# TLC5955.net
KiCad netlist of a schematic drawn in Altium Designer
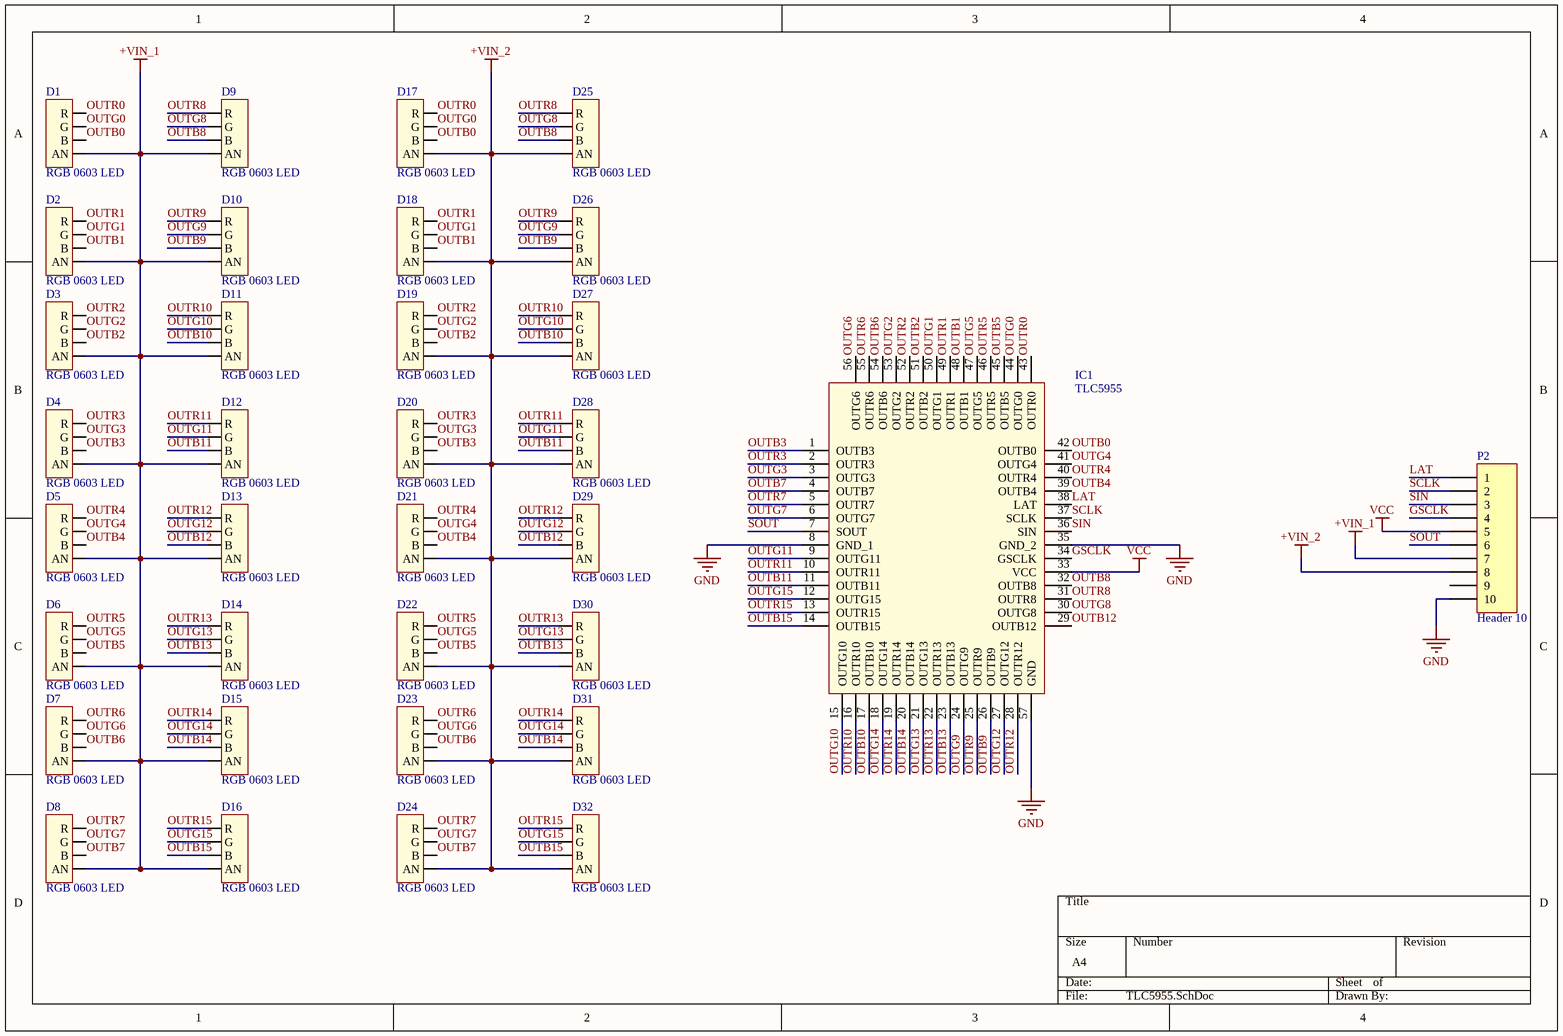
[diagram p0: TLC5955.SchDoc]

(export (version "E")
  (design (tool "Eeschema 10.0.6"))
  (components
    (comp (ref "D1")
      (value "RGB 0603 LED")
      (footprint "RGB LED")
      (libsource (lib "Schlib1") (part "RGB 0603 LED"))
    )
    (comp (ref "D2")
      (value "RGB 0603 LED")
      (footprint "RGB LED")
      (libsource (lib "Schlib1") (part "RGB 0603 LED"))
    )
    (comp (ref "D3")
      (value "RGB 0603 LED")
      (footprint "RGB LED")
      (libsource (lib "Schlib1") (part "RGB 0603 LED"))
    )
    (comp (ref "D4")
      (value "RGB 0603 LED")
      (footprint "RGB LED")
      (libsource (lib "Schlib1") (part "RGB 0603 LED"))
    )
    (comp (ref "D5")
      (value "RGB 0603 LED")
      (footprint "RGB LED")
      (libsource (lib "Schlib1") (part "RGB 0603 LED"))
    )
    (comp (ref "D6")
      (value "RGB 0603 LED")
      (footprint "RGB LED")
      (libsource (lib "Schlib1") (part "RGB 0603 LED"))
    )
    (comp (ref "D7")
      (value "RGB 0603 LED")
      (footprint "RGB LED")
      (libsource (lib "Schlib1") (part "RGB 0603 LED"))
    )
    (comp (ref "D8")
      (value "RGB 0603 LED")
      (footprint "RGB LED")
      (libsource (lib "Schlib1") (part "RGB 0603 LED"))
    )
    (comp (ref "D9")
      (value "RGB 0603 LED")
      (footprint "RGB LED")
      (libsource (lib "") (part "RGB 0603 LED_1"))
    )
    (comp (ref "D10")
      (value "RGB 0603 LED")
      (footprint "RGB LED")
      (libsource (lib "") (part "RGB 0603 LED_1"))
    )
    (comp (ref "D11")
      (value "RGB 0603 LED")
      (footprint "RGB LED")
      (libsource (lib "") (part "RGB 0603 LED_1"))
    )
    (comp (ref "D12")
      (value "RGB 0603 LED")
      (footprint "RGB LED")
      (libsource (lib "") (part "RGB 0603 LED_1"))
    )
    (comp (ref "D13")
      (value "RGB 0603 LED")
      (footprint "RGB LED")
      (libsource (lib "") (part "RGB 0603 LED_1"))
    )
    (comp (ref "D14")
      (value "RGB 0603 LED")
      (footprint "RGB LED")
      (libsource (lib "") (part "RGB 0603 LED_1"))
    )
    (comp (ref "D15")
      (value "RGB 0603 LED")
      (footprint "RGB LED")
      (libsource (lib "") (part "RGB 0603 LED_1"))
    )
    (comp (ref "D16")
      (value "RGB 0603 LED")
      (footprint "RGB LED")
      (libsource (lib "") (part "RGB 0603 LED_1"))
    )
    (comp (ref "D17")
      (value "RGB 0603 LED")
      (footprint "RGB LED")
      (libsource (lib "Schlib1") (part "RGB 0603 LED"))
    )
    (comp (ref "D18")
      (value "RGB 0603 LED")
      (footprint "RGB LED")
      (libsource (lib "Schlib1") (part "RGB 0603 LED"))
    )
    (comp (ref "D19")
      (value "RGB 0603 LED")
      (footprint "RGB LED")
      (libsource (lib "Schlib1") (part "RGB 0603 LED"))
    )
    (comp (ref "D20")
      (value "RGB 0603 LED")
      (footprint "RGB LED")
      (libsource (lib "Schlib1") (part "RGB 0603 LED"))
    )
    (comp (ref "D21")
      (value "RGB 0603 LED")
      (footprint "RGB LED")
      (libsource (lib "Schlib1") (part "RGB 0603 LED"))
    )
    (comp (ref "D22")
      (value "RGB 0603 LED")
      (footprint "RGB LED")
      (libsource (lib "Schlib1") (part "RGB 0603 LED"))
    )
    (comp (ref "D23")
      (value "RGB 0603 LED")
      (footprint "RGB LED")
      (libsource (lib "Schlib1") (part "RGB 0603 LED"))
    )
    (comp (ref "D24")
      (value "RGB 0603 LED")
      (footprint "RGB LED")
      (libsource (lib "Schlib1") (part "RGB 0603 LED"))
    )
    (comp (ref "D25")
      (value "RGB 0603 LED")
      (footprint "RGB LED")
      (libsource (lib "") (part "RGB 0603 LED_1"))
    )
    (comp (ref "D26")
      (value "RGB 0603 LED")
      (footprint "RGB LED")
      (libsource (lib "") (part "RGB 0603 LED_1"))
    )
    (comp (ref "D27")
      (value "RGB 0603 LED")
      (footprint "RGB LED")
      (libsource (lib "") (part "RGB 0603 LED_1"))
    )
    (comp (ref "D28")
      (value "RGB 0603 LED")
      (footprint "RGB LED")
      (libsource (lib "") (part "RGB 0603 LED_1"))
    )
    (comp (ref "D29")
      (value "RGB 0603 LED")
      (footprint "RGB LED")
      (libsource (lib "") (part "RGB 0603 LED_1"))
    )
    (comp (ref "D30")
      (value "RGB 0603 LED")
      (footprint "RGB LED")
      (libsource (lib "") (part "RGB 0603 LED_1"))
    )
    (comp (ref "D31")
      (value "RGB 0603 LED")
      (footprint "RGB LED")
      (libsource (lib "") (part "RGB 0603 LED_1"))
    )
    (comp (ref "D32")
      (value "RGB 0603 LED")
      (footprint "RGB LED")
      (libsource (lib "") (part "RGB 0603 LED_1"))
    )
    (comp (ref "IC1") (value "TLC5955") (footprint "TLC5955") (libsource (lib "Schlib1") (part "TLC5955")))
    (comp (ref "P2")
      (value "Header 10")
      (footprint "HDR1X10")
      (description "Header, 10-Pin")
      (fields (field (name "PUBLISHER") "Altium Limited"))
      (libsource (lib "Miscellaneous Connectors") (part "Header 10"))
    )
  )
  (nets
    (net (code "1") (name "+VIN_1") (class "Default")
      (node (ref "D1") (pin "4") (pinfunction "AN_4") (pintype "passive"))
      (node (ref "D10") (pin "4") (pinfunction "AN_4") (pintype "passive"))
      (node (ref "D11") (pin "4") (pinfunction "AN_4") (pintype "passive"))
      (node (ref "D12") (pin "4") (pinfunction "AN_4") (pintype "passive"))
      (node (ref "D13") (pin "4") (pinfunction "AN_4") (pintype "passive"))
      (node (ref "D14") (pin "4") (pinfunction "AN_4") (pintype "passive"))
      (node (ref "D15") (pin "4") (pinfunction "AN_4") (pintype "passive"))
      (node (ref "D16") (pin "4") (pinfunction "AN_4") (pintype "passive"))
      (node (ref "D2") (pin "4") (pinfunction "AN_4") (pintype "passive"))
      (node (ref "D3") (pin "4") (pinfunction "AN_4") (pintype "passive"))
      (node (ref "D4") (pin "4") (pinfunction "AN_4") (pintype "passive"))
      (node (ref "D5") (pin "4") (pinfunction "AN_4") (pintype "passive"))
      (node (ref "D6") (pin "4") (pinfunction "AN_4") (pintype "passive"))
      (node (ref "D7") (pin "4") (pinfunction "AN_4") (pintype "passive"))
      (node (ref "D8") (pin "4") (pinfunction "AN_4") (pintype "passive"))
      (node (ref "D9") (pin "4") (pinfunction "AN_4") (pintype "passive"))
      (node (ref "P2") (pin "7") (pinfunction "7_7") (pintype "passive"))
    )
    (net (code "2") (name "+VIN_2") (class "Default")
      (node (ref "D17") (pin "4") (pinfunction "AN_4") (pintype "passive"))
      (node (ref "D18") (pin "4") (pinfunction "AN_4") (pintype "passive"))
      (node (ref "D19") (pin "4") (pinfunction "AN_4") (pintype "passive"))
      (node (ref "D20") (pin "4") (pinfunction "AN_4") (pintype "passive"))
      (node (ref "D21") (pin "4") (pinfunction "AN_4") (pintype "passive"))
      (node (ref "D22") (pin "4") (pinfunction "AN_4") (pintype "passive"))
      (node (ref "D23") (pin "4") (pinfunction "AN_4") (pintype "passive"))
      (node (ref "D24") (pin "4") (pinfunction "AN_4") (pintype "passive"))
      (node (ref "D25") (pin "4") (pinfunction "AN_4") (pintype "passive"))
      (node (ref "D26") (pin "4") (pinfunction "AN_4") (pintype "passive"))
      (node (ref "D27") (pin "4") (pinfunction "AN_4") (pintype "passive"))
      (node (ref "D28") (pin "4") (pinfunction "AN_4") (pintype "passive"))
      (node (ref "D29") (pin "4") (pinfunction "AN_4") (pintype "passive"))
      (node (ref "D30") (pin "4") (pinfunction "AN_4") (pintype "passive"))
      (node (ref "D31") (pin "4") (pinfunction "AN_4") (pintype "passive"))
      (node (ref "D32") (pin "4") (pinfunction "AN_4") (pintype "passive"))
      (node (ref "P2") (pin "8") (pinfunction "8_8") (pintype "passive"))
    )
    (net (code "3") (name "/GSCLK") (class "Default")
      (node (ref "IC1") (pin "34") (pinfunction "GSCLK_34") (pintype "passive"))
      (node (ref "P2") (pin "4") (pinfunction "4_4") (pintype "passive"))
    )
    (net (code "4") (name "/LAT") (class "Default")
      (node (ref "IC1") (pin "38") (pinfunction "LAT_38") (pintype "passive"))
      (node (ref "P2") (pin "1") (pinfunction "1_1") (pintype "passive"))
    )
    (net (code "5") (name "/OUTB0") (class "Default")
      (node (ref "D1") (pin "3") (pinfunction "B_3") (pintype "passive"))
      (node (ref "D17") (pin "3") (pinfunction "B_3") (pintype "passive"))
      (node (ref "IC1") (pin "42") (pinfunction "OUTB0_42") (pintype "passive"))
    )
    (net (code "6") (name "/OUTB1") (class "Default")
      (node (ref "D18") (pin "3") (pinfunction "B_3") (pintype "passive"))
      (node (ref "D2") (pin "3") (pinfunction "B_3") (pintype "passive"))
      (node (ref "IC1") (pin "48") (pinfunction "OUTB1_48") (pintype "passive"))
    )
    (net (code "7") (name "/OUTB2") (class "Default")
      (node (ref "D19") (pin "3") (pinfunction "B_3") (pintype "passive"))
      (node (ref "D3") (pin "3") (pinfunction "B_3") (pintype "passive"))
      (node (ref "IC1") (pin "51") (pinfunction "OUTB2_51") (pintype "passive"))
    )
    (net (code "8") (name "/OUTB3") (class "Default")
      (node (ref "D20") (pin "3") (pinfunction "B_3") (pintype "passive"))
      (node (ref "D4") (pin "3") (pinfunction "B_3") (pintype "passive"))
      (node (ref "IC1") (pin "1") (pinfunction "OUTB3_1") (pintype "passive"))
    )
    (net (code "9") (name "/OUTB4") (class "Default")
      (node (ref "D21") (pin "3") (pinfunction "B_3") (pintype "passive"))
      (node (ref "D5") (pin "3") (pinfunction "B_3") (pintype "passive"))
      (node (ref "IC1") (pin "39") (pinfunction "OUTB4_39") (pintype "passive"))
    )
    (net (code "10") (name "/OUTB5") (class "Default")
      (node (ref "D22") (pin "3") (pinfunction "B_3") (pintype "passive"))
      (node (ref "D6") (pin "3") (pinfunction "B_3") (pintype "passive"))
      (node (ref "IC1") (pin "45") (pinfunction "OUTB5_45") (pintype "passive"))
    )
    (net (code "11") (name "/OUTB6") (class "Default")
      (node (ref "D23") (pin "3") (pinfunction "B_3") (pintype "passive"))
      (node (ref "D7") (pin "3") (pinfunction "B_3") (pintype "passive"))
      (node (ref "IC1") (pin "54") (pinfunction "OUTB6_54") (pintype "passive"))
    )
    (net (code "12") (name "/OUTB7") (class "Default")
      (node (ref "D24") (pin "3") (pinfunction "B_3") (pintype "passive"))
      (node (ref "D8") (pin "3") (pinfunction "B_3") (pintype "passive"))
      (node (ref "IC1") (pin "4") (pinfunction "OUTB7_4") (pintype "passive"))
    )
    (net (code "13") (name "/OUTB8") (class "Default")
      (node (ref "D25") (pin "3") (pinfunction "B_3") (pintype "passive"))
      (node (ref "D9") (pin "3") (pinfunction "B_3") (pintype "passive"))
      (node (ref "IC1") (pin "32") (pinfunction "OUTB8_32") (pintype "passive"))
    )
    (net (code "14") (name "/OUTB9") (class "Default")
      (node (ref "D10") (pin "3") (pinfunction "B_3") (pintype "passive"))
      (node (ref "D26") (pin "3") (pinfunction "B_3") (pintype "passive"))
      (node (ref "IC1") (pin "26") (pinfunction "OUTB9_26") (pintype "passive"))
    )
    (net (code "15") (name "/OUTB10") (class "Default")
      (node (ref "D11") (pin "3") (pinfunction "B_3") (pintype "passive"))
      (node (ref "D27") (pin "3") (pinfunction "B_3") (pintype "passive"))
      (node (ref "IC1") (pin "17") (pinfunction "OUTB10_17") (pintype "passive"))
    )
    (net (code "16") (name "/OUTB11") (class "Default")
      (node (ref "D12") (pin "3") (pinfunction "B_3") (pintype "passive"))
      (node (ref "D28") (pin "3") (pinfunction "B_3") (pintype "passive"))
      (node (ref "IC1") (pin "11") (pinfunction "OUTB11_11") (pintype "passive"))
    )
    (net (code "17") (name "/OUTB12") (class "Default")
      (node (ref "D13") (pin "3") (pinfunction "B_3") (pintype "passive"))
      (node (ref "D29") (pin "3") (pinfunction "B_3") (pintype "passive"))
      (node (ref "IC1") (pin "29") (pinfunction "OUTB12_29") (pintype "passive"))
    )
    (net (code "18") (name "/OUTB13") (class "Default")
      (node (ref "D14") (pin "3") (pinfunction "B_3") (pintype "passive"))
      (node (ref "D30") (pin "3") (pinfunction "B_3") (pintype "passive"))
      (node (ref "IC1") (pin "23") (pinfunction "OUTB13_23") (pintype "passive"))
    )
    (net (code "19") (name "/OUTB14") (class "Default")
      (node (ref "D15") (pin "3") (pinfunction "B_3") (pintype "passive"))
      (node (ref "D31") (pin "3") (pinfunction "B_3") (pintype "passive"))
      (node (ref "IC1") (pin "20") (pinfunction "OUTB14_20") (pintype "passive"))
    )
    (net (code "20") (name "/OUTB15") (class "Default")
      (node (ref "D16") (pin "3") (pinfunction "B_3") (pintype "passive"))
      (node (ref "D32") (pin "3") (pinfunction "B_3") (pintype "passive"))
      (node (ref "IC1") (pin "14") (pinfunction "OUTB15_14") (pintype "passive"))
    )
    (net (code "21") (name "/OUTG0") (class "Default")
      (node (ref "D1") (pin "2") (pinfunction "G_2") (pintype "passive"))
      (node (ref "D17") (pin "2") (pinfunction "G_2") (pintype "passive"))
      (node (ref "IC1") (pin "44") (pinfunction "OUTG0_44") (pintype "passive"))
    )
    (net (code "22") (name "/OUTG1") (class "Default")
      (node (ref "D18") (pin "2") (pinfunction "G_2") (pintype "passive"))
      (node (ref "D2") (pin "2") (pinfunction "G_2") (pintype "passive"))
      (node (ref "IC1") (pin "50") (pinfunction "OUTG1_50") (pintype "passive"))
    )
    (net (code "23") (name "/OUTG2") (class "Default")
      (node (ref "D19") (pin "2") (pinfunction "G_2") (pintype "passive"))
      (node (ref "D3") (pin "2") (pinfunction "G_2") (pintype "passive"))
      (node (ref "IC1") (pin "53") (pinfunction "OUTG2_53") (pintype "passive"))
    )
    (net (code "24") (name "/OUTG3") (class "Default")
      (node (ref "D20") (pin "2") (pinfunction "G_2") (pintype "passive"))
      (node (ref "D4") (pin "2") (pinfunction "G_2") (pintype "passive"))
      (node (ref "IC1") (pin "3") (pinfunction "OUTG3_3") (pintype "passive"))
    )
    (net (code "25") (name "/OUTG4") (class "Default")
      (node (ref "D21") (pin "2") (pinfunction "G_2") (pintype "passive"))
      (node (ref "D5") (pin "2") (pinfunction "G_2") (pintype "passive"))
      (node (ref "IC1") (pin "41") (pinfunction "OUTG4_41") (pintype "passive"))
    )
    (net (code "26") (name "/OUTG5") (class "Default")
      (node (ref "D22") (pin "2") (pinfunction "G_2") (pintype "passive"))
      (node (ref "D6") (pin "2") (pinfunction "G_2") (pintype "passive"))
      (node (ref "IC1") (pin "47") (pinfunction "OUTG5_47") (pintype "passive"))
    )
    (net (code "27") (name "/OUTG6") (class "Default")
      (node (ref "D23") (pin "2") (pinfunction "G_2") (pintype "passive"))
      (node (ref "D7") (pin "2") (pinfunction "G_2") (pintype "passive"))
      (node (ref "IC1") (pin "56") (pinfunction "OUTG6_56") (pintype "passive"))
    )
    (net (code "28") (name "/OUTG7") (class "Default")
      (node (ref "D24") (pin "2") (pinfunction "G_2") (pintype "passive"))
      (node (ref "D8") (pin "2") (pinfunction "G_2") (pintype "passive"))
      (node (ref "IC1") (pin "6") (pinfunction "OUTG7_6") (pintype "passive"))
    )
    (net (code "29") (name "/OUTG8") (class "Default")
      (node (ref "D25") (pin "2") (pinfunction "G_2") (pintype "passive"))
      (node (ref "D9") (pin "2") (pinfunction "G_2") (pintype "passive"))
      (node (ref "IC1") (pin "30") (pinfunction "OUTG8_30") (pintype "passive"))
    )
    (net (code "30") (name "/OUTG9") (class "Default")
      (node (ref "D10") (pin "2") (pinfunction "G_2") (pintype "passive"))
      (node (ref "D26") (pin "2") (pinfunction "G_2") (pintype "passive"))
      (node (ref "IC1") (pin "24") (pinfunction "OUTG9_24") (pintype "passive"))
    )
    (net (code "31") (name "/OUTG10") (class "Default")
      (node (ref "D11") (pin "2") (pinfunction "G_2") (pintype "passive"))
      (node (ref "D27") (pin "2") (pinfunction "G_2") (pintype "passive"))
      (node (ref "IC1") (pin "15") (pinfunction "OUTG10_15") (pintype "passive"))
    )
    (net (code "32") (name "/OUTG11") (class "Default")
      (node (ref "D12") (pin "2") (pinfunction "G_2") (pintype "passive"))
      (node (ref "D28") (pin "2") (pinfunction "G_2") (pintype "passive"))
      (node (ref "IC1") (pin "9") (pinfunction "OUTG11_9") (pintype "passive"))
    )
    (net (code "33") (name "/OUTG12") (class "Default")
      (node (ref "D13") (pin "2") (pinfunction "G_2") (pintype "passive"))
      (node (ref "D29") (pin "2") (pinfunction "G_2") (pintype "passive"))
      (node (ref "IC1") (pin "27") (pinfunction "OUTG12_27") (pintype "passive"))
    )
    (net (code "34") (name "/OUTG13") (class "Default")
      (node (ref "D14") (pin "2") (pinfunction "G_2") (pintype "passive"))
      (node (ref "D30") (pin "2") (pinfunction "G_2") (pintype "passive"))
      (node (ref "IC1") (pin "21") (pinfunction "OUTG13_21") (pintype "passive"))
    )
    (net (code "35") (name "/OUTG14") (class "Default")
      (node (ref "D15") (pin "2") (pinfunction "G_2") (pintype "passive"))
      (node (ref "D31") (pin "2") (pinfunction "G_2") (pintype "passive"))
      (node (ref "IC1") (pin "18") (pinfunction "OUTG14_18") (pintype "passive"))
    )
    (net (code "36") (name "/OUTG15") (class "Default")
      (node (ref "D16") (pin "2") (pinfunction "G_2") (pintype "passive"))
      (node (ref "D32") (pin "2") (pinfunction "G_2") (pintype "passive"))
      (node (ref "IC1") (pin "12") (pinfunction "OUTG15_12") (pintype "passive"))
    )
    (net (code "37") (name "/OUTR0") (class "Default")
      (node (ref "D1") (pin "1") (pinfunction "R_1") (pintype "passive"))
      (node (ref "D17") (pin "1") (pinfunction "R_1") (pintype "passive"))
      (node (ref "IC1") (pin "43") (pinfunction "OUTR0_43") (pintype "passive"))
    )
    (net (code "38") (name "/OUTR1") (class "Default")
      (node (ref "D18") (pin "1") (pinfunction "R_1") (pintype "passive"))
      (node (ref "D2") (pin "1") (pinfunction "R_1") (pintype "passive"))
      (node (ref "IC1") (pin "49") (pinfunction "OUTR1_49") (pintype "passive"))
    )
    (net (code "39") (name "/OUTR2") (class "Default")
      (node (ref "D19") (pin "1") (pinfunction "R_1") (pintype "passive"))
      (node (ref "D3") (pin "1") (pinfunction "R_1") (pintype "passive"))
      (node (ref "IC1") (pin "52") (pinfunction "OUTR2_52") (pintype "passive"))
    )
    (net (code "40") (name "/OUTR3") (class "Default")
      (node (ref "D20") (pin "1") (pinfunction "R_1") (pintype "passive"))
      (node (ref "D4") (pin "1") (pinfunction "R_1") (pintype "passive"))
      (node (ref "IC1") (pin "2") (pinfunction "OUTR3_2") (pintype "passive"))
    )
    (net (code "41") (name "/OUTR4") (class "Default")
      (node (ref "D21") (pin "1") (pinfunction "R_1") (pintype "passive"))
      (node (ref "D5") (pin "1") (pinfunction "R_1") (pintype "passive"))
      (node (ref "IC1") (pin "40") (pinfunction "OUTR4_40") (pintype "passive"))
    )
    (net (code "42") (name "/OUTR5") (class "Default")
      (node (ref "D22") (pin "1") (pinfunction "R_1") (pintype "passive"))
      (node (ref "D6") (pin "1") (pinfunction "R_1") (pintype "passive"))
      (node (ref "IC1") (pin "46") (pinfunction "OUTR5_46") (pintype "passive"))
    )
    (net (code "43") (name "/OUTR6") (class "Default")
      (node (ref "D23") (pin "1") (pinfunction "R_1") (pintype "passive"))
      (node (ref "D7") (pin "1") (pinfunction "R_1") (pintype "passive"))
      (node (ref "IC1") (pin "55") (pinfunction "OUTR6_55") (pintype "passive"))
    )
    (net (code "44") (name "/OUTR7") (class "Default")
      (node (ref "D24") (pin "1") (pinfunction "R_1") (pintype "passive"))
      (node (ref "D8") (pin "1") (pinfunction "R_1") (pintype "passive"))
      (node (ref "IC1") (pin "5") (pinfunction "OUTR7_5") (pintype "passive"))
    )
    (net (code "45") (name "/OUTR8") (class "Default")
      (node (ref "D25") (pin "1") (pinfunction "R_1") (pintype "passive"))
      (node (ref "D9") (pin "1") (pinfunction "R_1") (pintype "passive"))
      (node (ref "IC1") (pin "31") (pinfunction "OUTR8_31") (pintype "passive"))
    )
    (net (code "46") (name "/OUTR9") (class "Default")
      (node (ref "D10") (pin "1") (pinfunction "R_1") (pintype "passive"))
      (node (ref "D26") (pin "1") (pinfunction "R_1") (pintype "passive"))
      (node (ref "IC1") (pin "25") (pinfunction "OUTR9_25") (pintype "passive"))
    )
    (net (code "47") (name "/OUTR10") (class "Default")
      (node (ref "D11") (pin "1") (pinfunction "R_1") (pintype "passive"))
      (node (ref "D27") (pin "1") (pinfunction "R_1") (pintype "passive"))
      (node (ref "IC1") (pin "16") (pinfunction "OUTR10_16") (pintype "passive"))
    )
    (net (code "48") (name "/OUTR11") (class "Default")
      (node (ref "D12") (pin "1") (pinfunction "R_1") (pintype "passive"))
      (node (ref "D28") (pin "1") (pinfunction "R_1") (pintype "passive"))
      (node (ref "IC1") (pin "10") (pinfunction "OUTR11_10") (pintype "passive"))
    )
    (net (code "49") (name "/OUTR12") (class "Default")
      (node (ref "D13") (pin "1") (pinfunction "R_1") (pintype "passive"))
      (node (ref "D29") (pin "1") (pinfunction "R_1") (pintype "passive"))
      (node (ref "IC1") (pin "28") (pinfunction "OUTR12_28") (pintype "passive"))
    )
    (net (code "50") (name "/OUTR13") (class "Default")
      (node (ref "D14") (pin "1") (pinfunction "R_1") (pintype "passive"))
      (node (ref "D30") (pin "1") (pinfunction "R_1") (pintype "passive"))
      (node (ref "IC1") (pin "22") (pinfunction "OUTR13_22") (pintype "passive"))
    )
    (net (code "51") (name "/OUTR14") (class "Default")
      (node (ref "D15") (pin "1") (pinfunction "R_1") (pintype "passive"))
      (node (ref "D31") (pin "1") (pinfunction "R_1") (pintype "passive"))
      (node (ref "IC1") (pin "19") (pinfunction "OUTR14_19") (pintype "passive"))
    )
    (net (code "52") (name "/OUTR15") (class "Default")
      (node (ref "D16") (pin "1") (pinfunction "R_1") (pintype "passive"))
      (node (ref "D32") (pin "1") (pinfunction "R_1") (pintype "passive"))
      (node (ref "IC1") (pin "13") (pinfunction "OUTR15_13") (pintype "passive"))
    )
    (net (code "53") (name "/SCLK") (class "Default")
      (node (ref "IC1") (pin "37") (pinfunction "SCLK_37") (pintype "passive"))
      (node (ref "P2") (pin "2") (pinfunction "2_2") (pintype "passive"))
    )
    (net (code "54") (name "/SIN") (class "Default")
      (node (ref "IC1") (pin "36") (pinfunction "SIN_36") (pintype "passive"))
      (node (ref "P2") (pin "3") (pinfunction "3_3") (pintype "passive"))
    )
    (net (code "55") (name "/SOUT") (class "Default")
      (node (ref "IC1") (pin "7") (pinfunction "SOUT_7") (pintype "passive"))
      (node (ref "P2") (pin "6") (pinfunction "6_6") (pintype "passive"))
    )
    (net (code "56") (name "GND") (class "Default")
      (node (ref "IC1") (pin "35") (pinfunction "GND_2_35") (pintype "passive"))
      (node (ref "IC1") (pin "57") (pinfunction "GND_57") (pintype "passive"))
      (node (ref "IC1") (pin "8") (pinfunction "GND_1_8") (pintype "passive"))
      (node (ref "P2") (pin "10") (pinfunction "10_10") (pintype "passive"))
    )
    (net (code "57") (name "VCC") (class "Default")
      (node (ref "IC1") (pin "33") (pinfunction "VCC_33") (pintype "passive"))
      (node (ref "P2") (pin "5") (pinfunction "5_5") (pintype "passive"))
    )
    (net (code "58") (name "unconnected-(P2-Pad9)") (class "Default")
      (node (ref "P2") (pin "9") (pinfunction "9_9") (pintype "passive"))
    )
  )
)
